# 1-Schematic_Inverter.net
KiCad netlist of a schematic drawn in EasyEDA
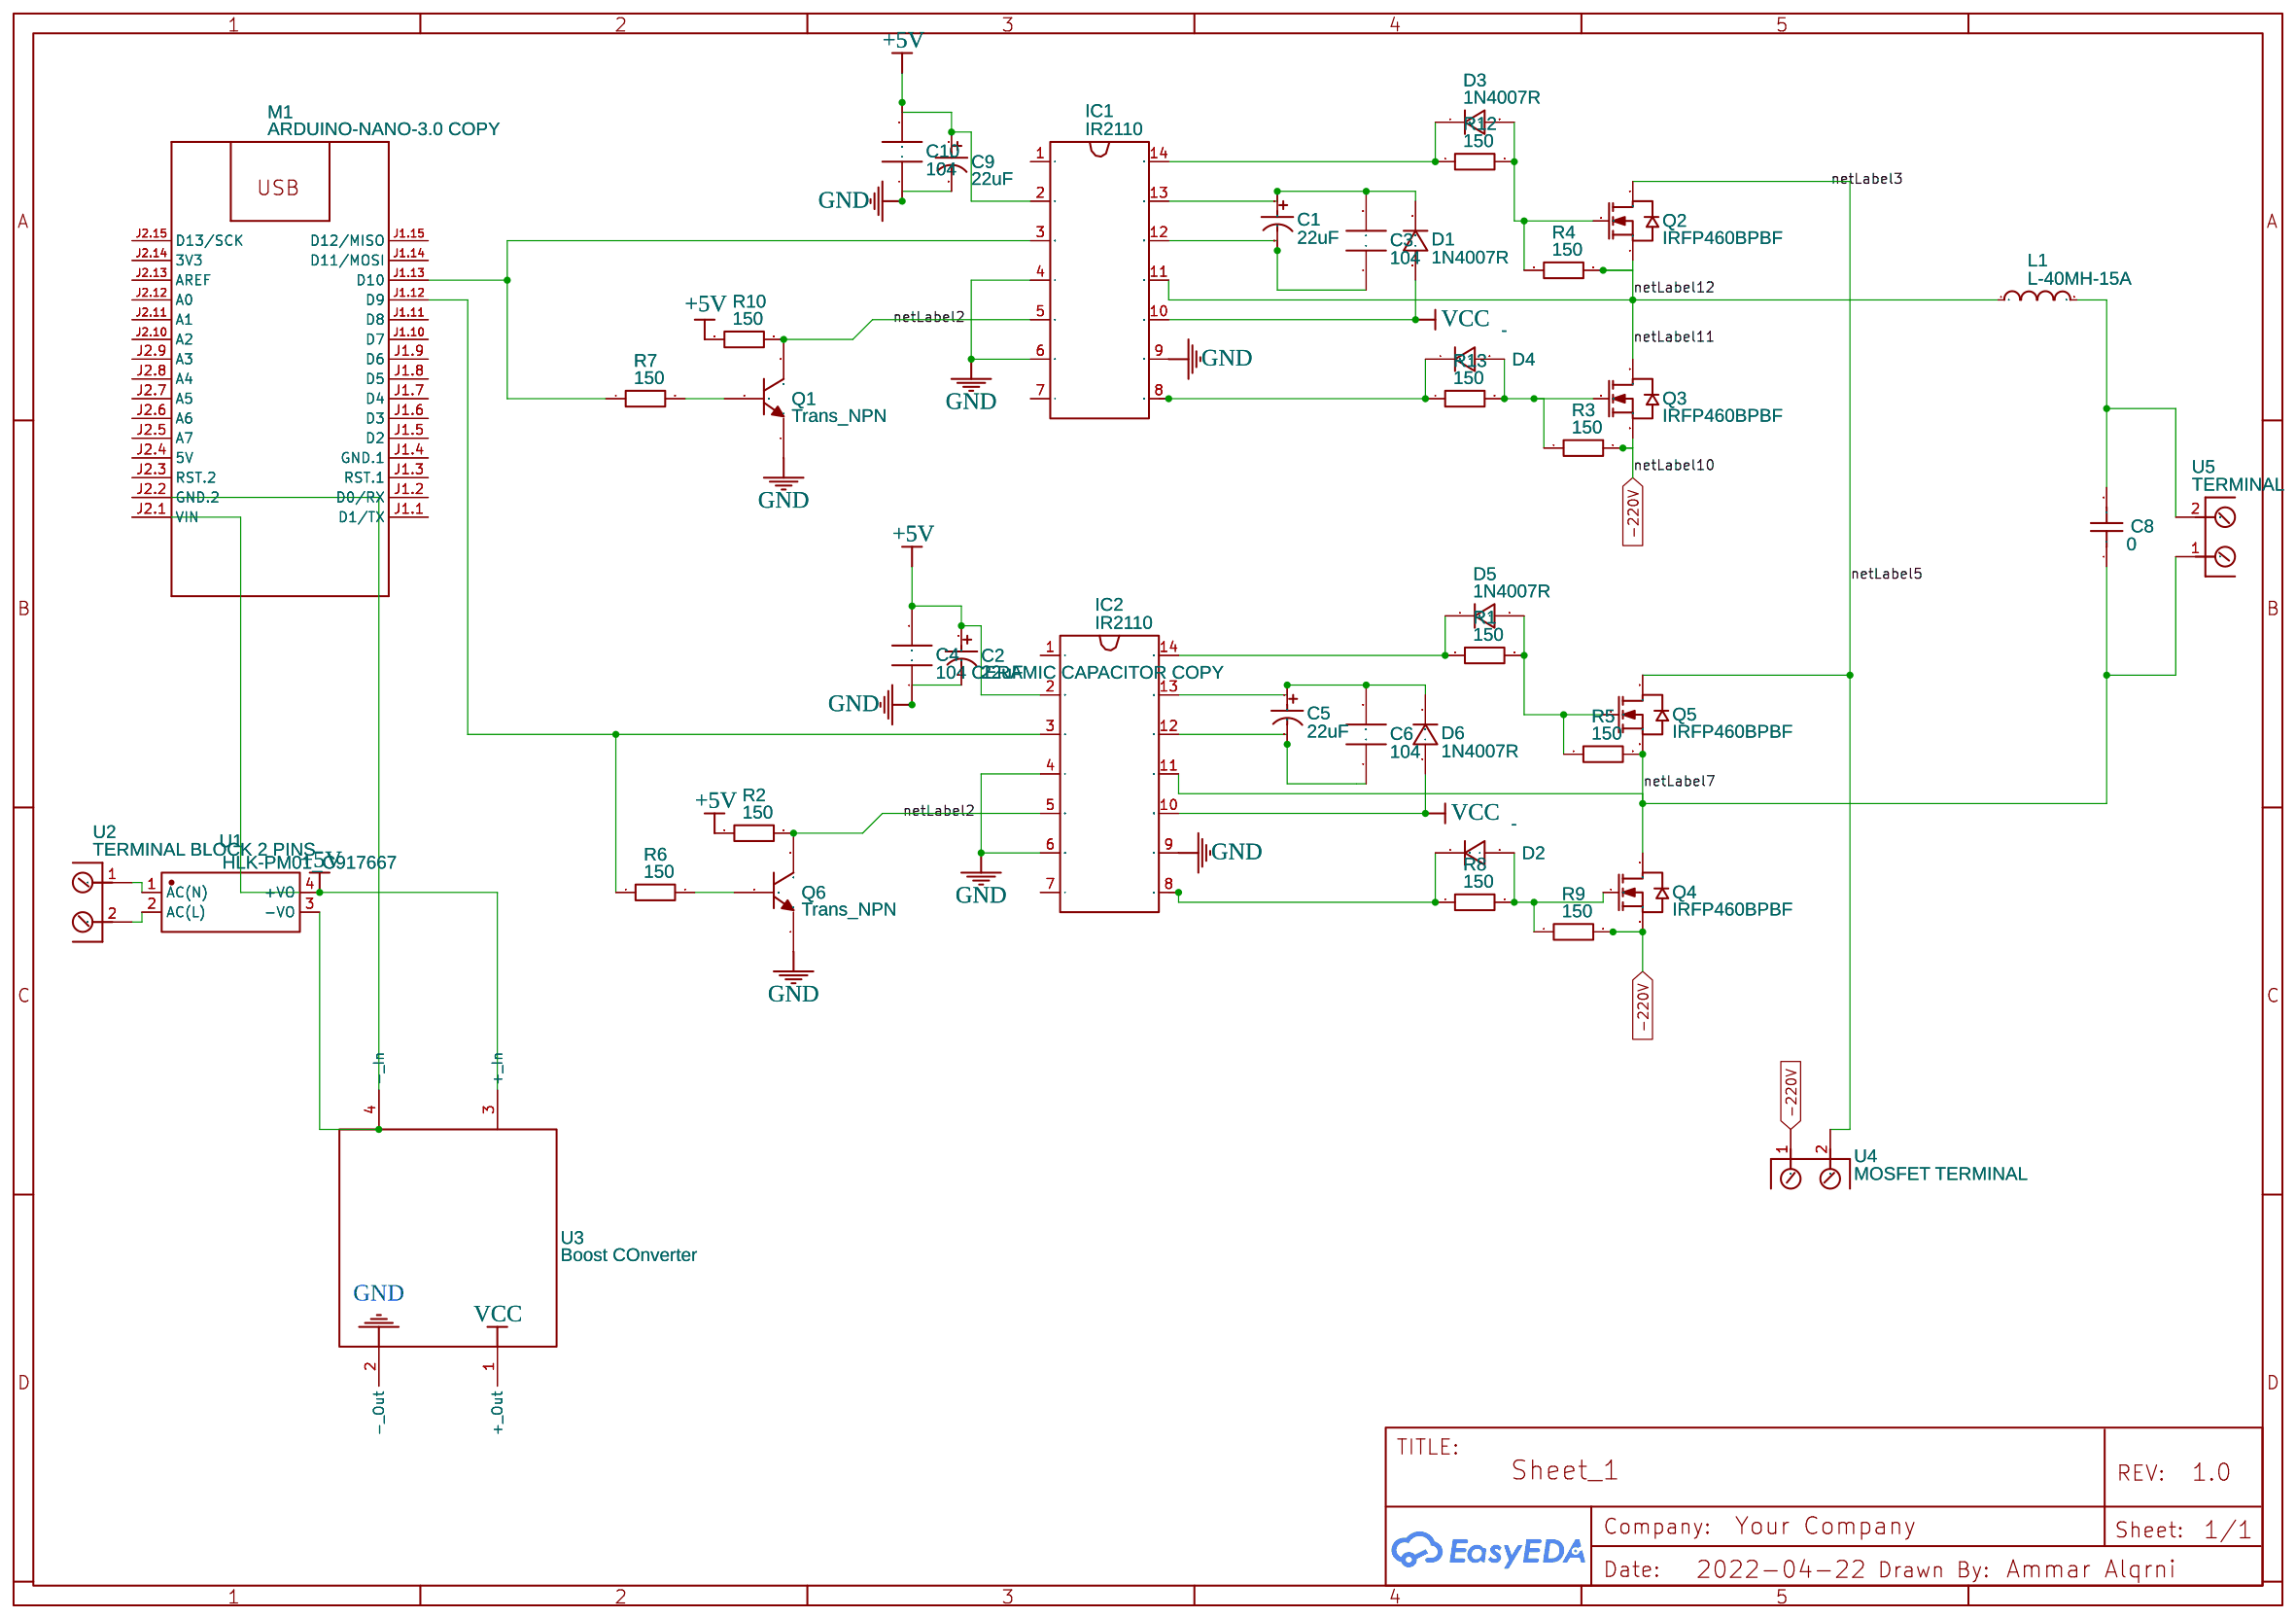
[diagram p0: schematic sheet]

(export (version "E")
  (design (tool "Eeschema 10.0.6"))
  (components
    (comp (ref "C1")
      (value "22uF")
      (fields (field (name "BOM_Manufacturer Part") "22UF 50V") (field (name "BOM_Supplier Part") "C28057"))
      (libsource (lib "") (part "22uF"))
    )
    (comp (ref "C2")
      (value "22uF")
      (fields (field (name "BOM_Manufacturer Part") "22UF 50V") (field (name "BOM_Supplier Part") "C28057"))
      (libsource (lib "") (part "22uF"))
    )
    (comp (ref "C3") (value "104") (libsource (lib "") (part "104 CERAMIC CAPACITOR COPY")))
    (comp (ref "C4")
      (value "104 CERAMIC CAPACITOR COPY")
      (libsource (lib "") (part "104 CERAMIC CAPACITOR COPY"))
    )
    (comp (ref "C5")
      (value "22uF")
      (fields (field (name "BOM_Manufacturer Part") "22UF 50V") (field (name "BOM_Supplier Part") "C28057"))
      (libsource (lib "") (part "22uF"))
    )
    (comp (ref "C6") (value "104") (libsource (lib "") (part "104 CERAMIC CAPACITOR COPY")))
    (comp (ref "C8")
      (value "0")
      (fields
        (field (name "BOM_Manufacturer Part") "CBB22474J630V")
        (field (name "BOM_Supplier Part") "C44081")
      )
      (libsource (lib "") (part "CBB22-225J400V"))
    )
    (comp (ref "C9")
      (value "22uF")
      (fields (field (name "BOM_Manufacturer Part") "22UF 50V") (field (name "BOM_Supplier Part") "C28057"))
      (libsource (lib "") (part "22uF"))
    )
    (comp (ref "C10") (value "104") (libsource (lib "") (part "104 CERAMIC CAPACITOR COPY")))
    (comp (ref "D1")
      (value "1N4007R")
      (fields (field (name "BOM_Supplier Part") "C432606"))
      (libsource (lib "") (part "1N4007R"))
    )
    (comp (ref "D2")
      (value "-")
      (fields (field (name "BOM_Manufacturer Part") "1N4007R") (field (name "BOM_Supplier Part") "C432606"))
      (libsource (lib "") (part "1N4007R_1"))
    )
    (comp (ref "D3")
      (value "1N4007R")
      (fields (field (name "BOM_Supplier Part") "C432606"))
      (libsource (lib "") (part "1N4007R_1"))
    )
    (comp (ref "D4")
      (value "-")
      (fields (field (name "BOM_Manufacturer Part") "1N4007R") (field (name "BOM_Supplier Part") "C432606"))
      (libsource (lib "") (part "1N4007R_1"))
    )
    (comp (ref "D5")
      (value "1N4007R")
      (fields (field (name "BOM_Supplier Part") "C432606"))
      (libsource (lib "") (part "1N4007R_1"))
    )
    (comp (ref "D6")
      (value "1N4007R")
      (fields (field (name "BOM_Supplier Part") "C432606"))
      (libsource (lib "") (part "1N4007R"))
    )
    (comp (ref "IC1") (value "IR2110") (libsource (lib "") (part "IR2110")))
    (comp (ref "IC2") (value "IR2110") (libsource (lib "") (part "IR2110")))
    (comp (ref "L1")
      (value "L-40MH-15A")
      (fields (field (name "BOM_Manufacturer Part") "General Inductor(TH)/10uH电感"))
      (libsource (lib "") (part "L-40MH-15A"))
    )
    (comp (ref "M1") (value "ARDUINO-NANO-3.0 COPY") (libsource (lib "") (part "ARDUINO-NANO-3.0 COPY")))
    (comp (ref "Q1") (value "Trans_NPN") (libsource (lib "") (part "Trans_NPN")))
    (comp (ref "Q2")
      (value "IRFP460BPBF")
      (fields (field (name "BOM_Supplier Part") "C428743"))
      (libsource (lib "") (part "IRFP460BPBF"))
    )
    (comp (ref "Q3")
      (value "IRFP460BPBF")
      (fields (field (name "BOM_Supplier Part") "C428743"))
      (libsource (lib "") (part "IRFP460BPBF"))
    )
    (comp (ref "Q4")
      (value "IRFP460BPBF")
      (fields (field (name "BOM_Supplier Part") "C428743"))
      (libsource (lib "") (part "IRFP460BPBF"))
    )
    (comp (ref "Q5")
      (value "IRFP460BPBF")
      (fields (field (name "BOM_Supplier Part") "C428743"))
      (libsource (lib "") (part "IRFP460BPBF"))
    )
    (comp (ref "Q6") (value "Trans_NPN") (libsource (lib "") (part "Trans_NPN")))
    (comp (ref "R1") (value "150") (libsource (lib "") (part "150")))
    (comp (ref "R2") (value "150") (libsource (lib "") (part "150")))
    (comp (ref "R3") (value "150") (libsource (lib "") (part "150")))
    (comp (ref "R4") (value "150") (libsource (lib "") (part "150")))
    (comp (ref "R5") (value "150") (libsource (lib "") (part "150")))
    (comp (ref "R6") (value "150") (libsource (lib "") (part "150")))
    (comp (ref "R7") (value "150") (libsource (lib "") (part "150")))
    (comp (ref "R8") (value "150") (libsource (lib "") (part "150")))
    (comp (ref "R9") (value "150") (libsource (lib "") (part "150")))
    (comp (ref "R10") (value "150") (libsource (lib "") (part "150")))
    (comp (ref "R12") (value "150") (libsource (lib "") (part "150")))
    (comp (ref "R13") (value "150") (libsource (lib "") (part "150")))
    (comp (ref "U1")
      (value "HLK-PM01_C917667")
      (fields (field (name "BOM_Manufacturer Part") "HLK-PM01") (field (name "BOM_Supplier Part") "C917667"))
      (libsource (lib "") (part "HLK-PM01_C917667"))
    )
    (comp (ref "U2") (value "TERMINAL BLOCK 2 PINS") (libsource (lib "") (part "TERMINAL BLOCK 2 PINS_1")))
    (comp (ref "U3") (value "Boost COnverter") (libsource (lib "") (part "Boost COnverter")))
    (comp (ref "U4") (value "MOSFET TERMINAL") (libsource (lib "") (part "TERMINAL BLOCK 2 PINS_2")))
    (comp (ref "U5") (value "TERMINAL") (libsource (lib "") (part "TERMINAL BLOCK 2 PINS")))
  )
  (nets
    (net (code "1") (name "+5V") (class "Default")
      (node (ref "C10") (pin "2") (pinfunction "2_2") (pintype "unspecified"))
      (node (ref "C2") (pin "1") (pinfunction "1_1") (pintype "input"))
      (node (ref "C4") (pin "2") (pinfunction "2_2") (pintype "unspecified"))
      (node (ref "C9") (pin "1") (pinfunction "1_1") (pintype "input"))
      (node (ref "IC1") (pin "2") (pinfunction "2_2") (pintype "unspecified"))
      (node (ref "IC2") (pin "2") (pinfunction "2_2") (pintype "unspecified"))
      (node (ref "R10") (pin "1") (pintype "unspecified"))
      (node (ref "R2") (pin "1") (pintype "unspecified"))
      (node (ref "U1") (pin "4") (pinfunction "+VO_4") (pintype "unspecified"))
      (node (ref "U3") (pin "3") (pinfunction "+_In_3") (pintype "unspecified"))
    )
    (net (code "2") (name "-220V") (class "Default")
      (node (ref "Q3") (pin "3") (pinfunction "S_3") (pintype "unspecified"))
      (node (ref "Q4") (pin "3") (pinfunction "S_3") (pintype "unspecified"))
      (node (ref "R3") (pin "2") (pintype "unspecified"))
      (node (ref "R9") (pin "2") (pintype "unspecified"))
      (node (ref "U4") (pin "1") (pinfunction "1_1") (pintype "unspecified"))
    )
    (net (code "3") (name "/netLabel2") (class "Default")
      (node (ref "IC1") (pin "5") (pinfunction "5_5") (pintype "unspecified"))
      (node (ref "IC2") (pin "5") (pinfunction "5_5") (pintype "unspecified"))
      (node (ref "Q1") (pin "3") (pinfunction "C_3") (pintype "unspecified"))
      (node (ref "Q6") (pin "3") (pinfunction "C_3") (pintype "unspecified"))
      (node (ref "R10") (pin "2") (pintype "unspecified"))
      (node (ref "R2") (pin "2") (pintype "unspecified"))
    )
    (net (code "4") (name "/netLabel3") (class "Default")
      (node (ref "Q2") (pin "2") (pinfunction "D_2") (pintype "unspecified"))
      (node (ref "Q5") (pin "2") (pinfunction "D_2") (pintype "unspecified"))
      (node (ref "U4") (pin "2") (pinfunction "2_2") (pintype "unspecified"))
    )
    (net (code "5") (name "/netLabel7") (class "Default")
      (node (ref "C8") (pin "1") (pinfunction "1_1") (pintype "unspecified"))
      (node (ref "IC2") (pin "11") (pinfunction "11_11") (pintype "unspecified"))
      (node (ref "Q4") (pin "2") (pinfunction "D_2") (pintype "unspecified"))
      (node (ref "Q5") (pin "3") (pinfunction "S_3") (pintype "unspecified"))
      (node (ref "R5") (pin "2") (pintype "unspecified"))
      (node (ref "U5") (pin "1") (pinfunction "1_1") (pintype "unspecified"))
    )
    (net (code "6") (name "/netLabel11") (class "Default")
      (node (ref "IC1") (pin "11") (pinfunction "11_11") (pintype "unspecified"))
      (node (ref "L1") (pin "1") (pinfunction "1_1") (pintype "unspecified"))
      (node (ref "Q2") (pin "3") (pinfunction "S_3") (pintype "unspecified"))
      (node (ref "Q3") (pin "2") (pinfunction "D_2") (pintype "unspecified"))
      (node (ref "R4") (pin "2") (pintype "unspecified"))
    )
    (net (code "7") (name "GND") (class "Default")
      (node (ref "C10") (pin "1") (pinfunction "1_1") (pintype "unspecified"))
      (node (ref "C2") (pin "2") (pinfunction "2_2") (pintype "input"))
      (node (ref "C4") (pin "1") (pinfunction "1_1") (pintype "unspecified"))
      (node (ref "C9") (pin "2") (pinfunction "2_2") (pintype "input"))
      (node (ref "IC1") (pin "4") (pinfunction "4_4") (pintype "unspecified"))
      (node (ref "IC1") (pin "6") (pinfunction "6_6") (pintype "unspecified"))
      (node (ref "IC1") (pin "9") (pinfunction "9_9") (pintype "unspecified"))
      (node (ref "IC2") (pin "4") (pinfunction "4_4") (pintype "unspecified"))
      (node (ref "IC2") (pin "6") (pinfunction "6_6") (pintype "unspecified"))
      (node (ref "IC2") (pin "9") (pinfunction "9_9") (pintype "unspecified"))
      (node (ref "Q1") (pin "1") (pinfunction "E_1") (pintype "unspecified"))
      (node (ref "Q6") (pin "1") (pinfunction "E_1") (pintype "unspecified"))
      (node (ref "U3") (pin "2") (pinfunction "-_Out_2") (pintype "unspecified"))
    )
    (net (code "8") (name "Net-(C1-Pad2)") (class "Default")
      (node (ref "C1") (pin "2") (pinfunction "2_2") (pintype "input"))
      (node (ref "C3") (pin "1") (pinfunction "1_1") (pintype "unspecified"))
      (node (ref "IC1") (pin "12") (pinfunction "12_12") (pintype "unspecified"))
    )
    (net (code "9") (name "Net-(C5-Pad2)") (class "Default")
      (node (ref "C5") (pin "2") (pinfunction "2_2") (pintype "input"))
      (node (ref "C6") (pin "1") (pinfunction "1_1") (pintype "unspecified"))
      (node (ref "IC2") (pin "12") (pinfunction "12_12") (pintype "unspecified"))
    )
    (net (code "10") (name "Net-(C8-Pad2)") (class "Default")
      (node (ref "C8") (pin "2") (pinfunction "2_2") (pintype "unspecified"))
      (node (ref "L1") (pin "2") (pinfunction "2_2") (pintype "unspecified"))
      (node (ref "U5") (pin "2") (pinfunction "2_2") (pintype "unspecified"))
    )
    (net (code "11") (name "Net-(D1-C)") (class "Default")
      (node (ref "C1") (pin "1") (pinfunction "1_1") (pintype "input"))
      (node (ref "C3") (pin "2") (pinfunction "2_2") (pintype "unspecified"))
      (node (ref "D1") (pin "1") (pinfunction "C_1") (pintype "unspecified"))
      (node (ref "IC1") (pin "13") (pinfunction "13_13") (pintype "unspecified"))
    )
    (net (code "12") (name "Net-(D2-A)") (class "Default")
      (node (ref "D2") (pin "2") (pinfunction "A_2") (pintype "unspecified"))
      (node (ref "Q4") (pin "1") (pinfunction "G_1") (pintype "unspecified"))
      (node (ref "R8") (pin "2") (pintype "unspecified"))
      (node (ref "R9") (pin "1") (pintype "unspecified"))
    )
    (net (code "13") (name "Net-(D2-C)") (class "Default")
      (node (ref "D2") (pin "1") (pinfunction "C_1") (pintype "unspecified"))
      (node (ref "IC2") (pin "8") (pinfunction "8_8") (pintype "unspecified"))
      (node (ref "R8") (pin "1") (pintype "unspecified"))
    )
    (net (code "14") (name "Net-(D3-A)") (class "Default")
      (node (ref "D3") (pin "2") (pinfunction "A_2") (pintype "unspecified"))
      (node (ref "Q2") (pin "1") (pinfunction "G_1") (pintype "unspecified"))
      (node (ref "R12") (pin "2") (pintype "unspecified"))
      (node (ref "R4") (pin "1") (pintype "unspecified"))
    )
    (net (code "15") (name "Net-(D3-C)") (class "Default")
      (node (ref "D3") (pin "1") (pinfunction "C_1") (pintype "unspecified"))
      (node (ref "IC1") (pin "14") (pinfunction "14_14") (pintype "unspecified"))
      (node (ref "R12") (pin "1") (pintype "unspecified"))
    )
    (net (code "16") (name "Net-(D4-A)") (class "Default")
      (node (ref "D4") (pin "2") (pinfunction "A_2") (pintype "unspecified"))
      (node (ref "Q3") (pin "1") (pinfunction "G_1") (pintype "unspecified"))
      (node (ref "R13") (pin "2") (pintype "unspecified"))
      (node (ref "R3") (pin "1") (pintype "unspecified"))
    )
    (net (code "17") (name "Net-(D4-C)") (class "Default")
      (node (ref "D4") (pin "1") (pinfunction "C_1") (pintype "unspecified"))
      (node (ref "IC1") (pin "8") (pinfunction "8_8") (pintype "unspecified"))
      (node (ref "R13") (pin "1") (pintype "unspecified"))
    )
    (net (code "18") (name "Net-(D5-A)") (class "Default")
      (node (ref "D5") (pin "2") (pinfunction "A_2") (pintype "unspecified"))
      (node (ref "Q5") (pin "1") (pinfunction "G_1") (pintype "unspecified"))
      (node (ref "R1") (pin "2") (pintype "unspecified"))
      (node (ref "R5") (pin "1") (pintype "unspecified"))
    )
    (net (code "19") (name "Net-(D5-C)") (class "Default")
      (node (ref "D5") (pin "1") (pinfunction "C_1") (pintype "unspecified"))
      (node (ref "IC2") (pin "14") (pinfunction "14_14") (pintype "unspecified"))
      (node (ref "R1") (pin "1") (pintype "unspecified"))
    )
    (net (code "20") (name "Net-(D6-C)") (class "Default")
      (node (ref "C5") (pin "1") (pinfunction "1_1") (pintype "input"))
      (node (ref "C6") (pin "2") (pinfunction "2_2") (pintype "unspecified"))
      (node (ref "D6") (pin "1") (pinfunction "C_1") (pintype "unspecified"))
      (node (ref "IC2") (pin "13") (pinfunction "13_13") (pintype "unspecified"))
    )
    (net (code "21") (name "Net-(M1-D9)") (class "Default")
      (node (ref "IC2") (pin "3") (pinfunction "3_3") (pintype "unspecified"))
      (node (ref "M1") (pin "J1.12") (pinfunction "D9_J1.12") (pintype "bidirectional"))
      (node (ref "R6") (pin "1") (pintype "unspecified"))
    )
    (net (code "22") (name "Net-(M1-D10)") (class "Default")
      (node (ref "IC1") (pin "3") (pinfunction "3_3") (pintype "unspecified"))
      (node (ref "M1") (pin "J1.13") (pinfunction "D10_J1.13") (pintype "bidirectional"))
      (node (ref "R7") (pin "1") (pintype "unspecified"))
    )
    (net (code "23") (name "Net-(M1-GND.2)") (class "Default")
      (node (ref "M1") (pin "J2.2") (pinfunction "GND.2_J2.2") (pintype "bidirectional"))
      (node (ref "U1") (pin "3") (pinfunction "-VO_3") (pintype "unspecified"))
      (node (ref "U3") (pin "4") (pinfunction "-_In_4") (pintype "unspecified"))
    )
    (net (code "24") (name "Net-(Q1-B)") (class "Default")
      (node (ref "Q1") (pin "2") (pinfunction "B_2") (pintype "unspecified"))
      (node (ref "R7") (pin "2") (pintype "unspecified"))
    )
    (net (code "25") (name "Net-(Q6-B)") (class "Default")
      (node (ref "Q6") (pin "2") (pinfunction "B_2") (pintype "unspecified"))
      (node (ref "R6") (pin "2") (pintype "unspecified"))
    )
    (net (code "26") (name "Net-(U1-AC(L))") (class "Default")
      (node (ref "U1") (pin "2") (pinfunction "AC(L)_2") (pintype "unspecified"))
      (node (ref "U2") (pin "2") (pinfunction "2_2") (pintype "unspecified"))
    )
    (net (code "27") (name "Net-(U1-AC(N))") (class "Default")
      (node (ref "U1") (pin "1") (pinfunction "AC(N)_1") (pintype "unspecified"))
      (node (ref "U2") (pin "1") (pinfunction "1_1") (pintype "unspecified"))
    )
    (net (code "28") (name "VCC") (class "Default")
      (node (ref "D1") (pin "2") (pinfunction "A_2") (pintype "unspecified"))
      (node (ref "D6") (pin "2") (pinfunction "A_2") (pintype "unspecified"))
      (node (ref "IC1") (pin "10") (pinfunction "10_10") (pintype "unspecified"))
      (node (ref "IC2") (pin "10") (pinfunction "10_10") (pintype "unspecified"))
      (node (ref "U3") (pin "1") (pinfunction "+_Out_1") (pintype "unspecified"))
    )
    (net (code "29") (name "unconnected-(IC1-Pad1)") (class "Default")
      (node (ref "IC1") (pin "1") (pinfunction "1_1") (pintype "unspecified"))
    )
    (net (code "30") (name "unconnected-(IC1-Pad7)") (class "Default")
      (node (ref "IC1") (pin "7") (pinfunction "7_7") (pintype "unspecified"))
    )
    (net (code "31") (name "unconnected-(IC2-Pad1)") (class "Default")
      (node (ref "IC2") (pin "1") (pinfunction "1_1") (pintype "unspecified"))
    )
    (net (code "32") (name "unconnected-(IC2-Pad7)") (class "Default")
      (node (ref "IC2") (pin "7") (pinfunction "7_7") (pintype "unspecified"))
    )
    (net (code "33") (name "unconnected-(M1-3V3-PadJ2.14)") (class "Default")
      (node (ref "M1") (pin "J2.14") (pinfunction "3V3_J2.14") (pintype "bidirectional"))
    )
    (net (code "34") (name "unconnected-(M1-5V-PadJ2.4)") (class "Default")
      (node (ref "M1") (pin "J2.4") (pinfunction "5V_J2.4") (pintype "bidirectional"))
    )
    (net (code "35") (name "unconnected-(M1-A0-PadJ2.12)") (class "Default")
      (node (ref "M1") (pin "J2.12") (pinfunction "A0_J2.12") (pintype "bidirectional"))
    )
    (net (code "36") (name "unconnected-(M1-A1-PadJ2.11)") (class "Default")
      (node (ref "M1") (pin "J2.11") (pinfunction "A1_J2.11") (pintype "bidirectional"))
    )
    (net (code "37") (name "unconnected-(M1-A2-PadJ2.10)") (class "Default")
      (node (ref "M1") (pin "J2.10") (pinfunction "A2_J2.10") (pintype "bidirectional"))
    )
    (net (code "38") (name "unconnected-(M1-A3-PadJ2.9)") (class "Default")
      (node (ref "M1") (pin "J2.9") (pinfunction "A3_J2.9") (pintype "bidirectional"))
    )
    (net (code "39") (name "unconnected-(M1-A4-PadJ2.8)") (class "Default")
      (node (ref "M1") (pin "J2.8") (pinfunction "A4_J2.8") (pintype "bidirectional"))
    )
    (net (code "40") (name "unconnected-(M1-A5-PadJ2.7)") (class "Default")
      (node (ref "M1") (pin "J2.7") (pinfunction "A5_J2.7") (pintype "bidirectional"))
    )
    (net (code "41") (name "unconnected-(M1-A6-PadJ2.6)") (class "Default")
      (node (ref "M1") (pin "J2.6") (pinfunction "A6_J2.6") (pintype "bidirectional"))
    )
    (net (code "42") (name "unconnected-(M1-A7-PadJ2.5)") (class "Default")
      (node (ref "M1") (pin "J2.5") (pinfunction "A7_J2.5") (pintype "bidirectional"))
    )
    (net (code "43") (name "unconnected-(M1-AREF-PadJ2.13)") (class "Default")
      (node (ref "M1") (pin "J2.13") (pinfunction "AREF_J2.13") (pintype "bidirectional"))
    )
    (net (code "44") (name "unconnected-(M1-D0{slash}RX-PadJ1.2)") (class "Default")
      (node (ref "M1") (pin "J1.2") (pinfunction "D0/RX_J1.2") (pintype "bidirectional"))
    )
    (net (code "45") (name "unconnected-(M1-D1{slash}TX-PadJ1.1)") (class "Default")
      (node (ref "M1") (pin "J1.1") (pinfunction "D1/TX_J1.1") (pintype "bidirectional"))
    )
    (net (code "46") (name "unconnected-(M1-D2-PadJ1.5)") (class "Default")
      (node (ref "M1") (pin "J1.5") (pinfunction "D2_J1.5") (pintype "bidirectional"))
    )
    (net (code "47") (name "unconnected-(M1-D3-PadJ1.6)") (class "Default")
      (node (ref "M1") (pin "J1.6") (pinfunction "D3_J1.6") (pintype "bidirectional"))
    )
    (net (code "48") (name "unconnected-(M1-D4-PadJ1.7)") (class "Default")
      (node (ref "M1") (pin "J1.7") (pinfunction "D4_J1.7") (pintype "bidirectional"))
    )
    (net (code "49") (name "unconnected-(M1-D5-PadJ1.8)") (class "Default")
      (node (ref "M1") (pin "J1.8") (pinfunction "D5_J1.8") (pintype "bidirectional"))
    )
    (net (code "50") (name "unconnected-(M1-D6-PadJ1.9)") (class "Default")
      (node (ref "M1") (pin "J1.9") (pinfunction "D6_J1.9") (pintype "bidirectional"))
    )
    (net (code "51") (name "unconnected-(M1-D7-PadJ1.10)") (class "Default")
      (node (ref "M1") (pin "J1.10") (pinfunction "D7_J1.10") (pintype "bidirectional"))
    )
    (net (code "52") (name "unconnected-(M1-D8-PadJ1.11)") (class "Default")
      (node (ref "M1") (pin "J1.11") (pinfunction "D8_J1.11") (pintype "bidirectional"))
    )
    (net (code "53") (name "unconnected-(M1-D11{slash}MOSI-PadJ1.14)") (class "Default")
      (node (ref "M1") (pin "J1.14") (pinfunction "D11/MOSI_J1.14") (pintype "bidirectional"))
    )
    (net (code "54") (name "unconnected-(M1-D12{slash}MISO-PadJ1.15)") (class "Default")
      (node (ref "M1") (pin "J1.15") (pinfunction "D12/MISO_J1.15") (pintype "bidirectional"))
    )
    (net (code "55") (name "unconnected-(M1-D13{slash}SCK-PadJ2.15)") (class "Default")
      (node (ref "M1") (pin "J2.15") (pinfunction "D13/SCK_J2.15") (pintype "bidirectional"))
    )
    (net (code "56") (name "unconnected-(M1-GND.1-PadJ1.4)") (class "Default")
      (node (ref "M1") (pin "J1.4") (pinfunction "GND.1_J1.4") (pintype "bidirectional"))
    )
    (net (code "57") (name "unconnected-(M1-RST.1-PadJ1.3)") (class "Default")
      (node (ref "M1") (pin "J1.3") (pinfunction "RST.1_J1.3") (pintype "bidirectional"))
    )
    (net (code "58") (name "unconnected-(M1-RST.2-PadJ2.3)") (class "Default")
      (node (ref "M1") (pin "J2.3") (pinfunction "RST.2_J2.3") (pintype "bidirectional"))
    )
    (net (code "59") (name "unconnected-(M1-VIN-PadJ2.1)") (class "Default")
      (node (ref "M1") (pin "J2.1") (pinfunction "VIN_J2.1") (pintype "bidirectional"))
    )
  )
)
